# LB_i3_Button-v03_rev2.net
KiCad netlist of a schematic drawn in EAGLE
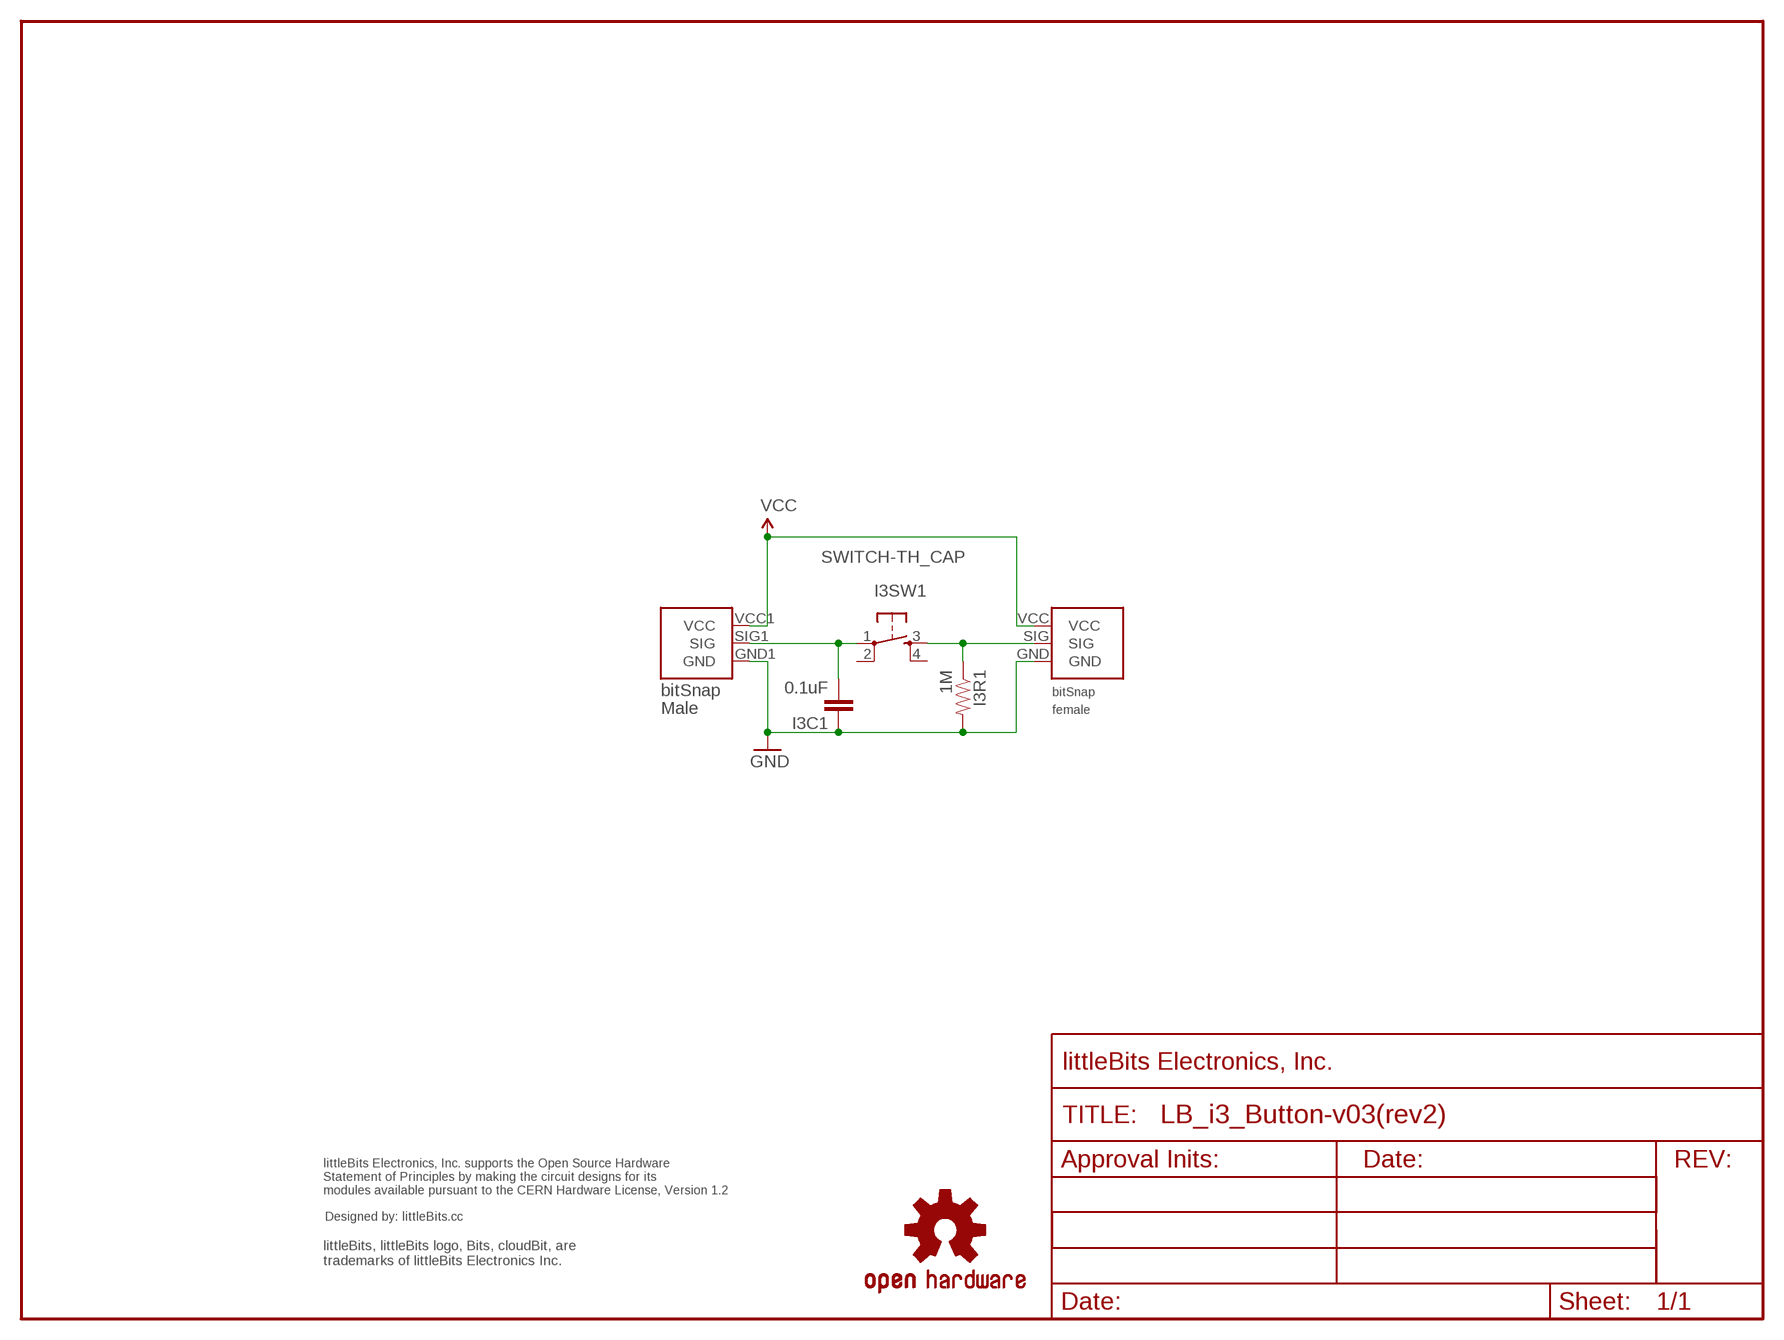
[diagram p0: schematic, sheet 1]

(export (version "E")
  (design (tool "Eeschema 10.0.6"))
  (components
    (comp (ref "I3BSF1")
      (value "BITSNAP_V03_FEMALE")
      (footprint "eagle-import:BITSNAP_V03_FEMALE")
      (libsource (lib "eagle-import") (part "BITSNAP_V03_FEMALE"))
    )
    (comp (ref "I3BSM1")
      (value "BITSNAP_V03_MALE")
      (footprint "eagle-import:BITSNAP_V03_MALE")
      (libsource (lib "eagle-import") (part "BITSNAP_V03_MALE"))
    )
    (comp (ref "I3C1")
      (value "0.1uF")
      (footprint "eagle-import:0603-CAP")
      (libsource (lib "eagle-import") (part "CAP0603-CAP"))
    )
    (comp (ref "I3R1")
      (value "1M")
      (footprint "eagle-import:0603-RES")
      (libsource (lib "eagle-import") (part "RESISTOR0603-RES"))
    )
    (comp (ref "I3SW1")
      (value "SWITCH-TH_CAP")
      (footprint "eagle-import:SWITCH-TH_CAP")
      (libsource (lib "eagle-import") (part "SWITCH-TH_CAP"))
    )
    (comp (ref "U$1")
      (value "OSHW-LOGOL")
      (footprint "eagle-import:OSHW-LOGO-L")
      (libsource (lib "eagle-import") (part "OSHW-LOGOL"))
    )
    (comp (ref "U$2")
      (value "FRAME-LETTER-OHWOHW")
      (footprint "eagle-import:FABDWG01-OHW")
      (libsource (lib "eagle-import") (part "FRAME-LETTER-OHWOHW"))
    )
    (comp (ref "U$5")
      (value "LB_CREDITS")
      (footprint "eagle-import:OSHWCREDIT")
      (libsource (lib "eagle-import") (part "LB_CREDITS"))
    )
  )
  (nets
    (net (code "1") (name "GND") (class "Default")
      (node (ref "I3BSF1") (pin "GND") (pinfunction "GND_GND") (pintype "bidirectional"))
      (node (ref "I3BSM1") (pin "GND1") (pinfunction "GND_GND1") (pintype "bidirectional"))
      (node (ref "I3C1") (pin "1") (pinfunction "1_1") (pintype "passive"))
      (node (ref "I3R1") (pin "2") (pinfunction "2_2") (pintype "passive"))
    )
    (net (code "2") (name "Net-(I3BSF1-PadSIG)") (class "Default")
      (node (ref "I3BSF1") (pin "SIG") (pinfunction "SIG_SIG") (pintype "bidirectional"))
      (node (ref "I3R1") (pin "1") (pinfunction "1_1") (pintype "passive"))
      (node (ref "I3SW1") (pin "3") (pinfunction "3_3") (pintype "passive"))
    )
    (net (code "3") (name "Net-(I3BSM1-SIG)") (class "Default")
      (node (ref "I3BSM1") (pin "SIG1") (pinfunction "SIG_SIG1") (pintype "bidirectional"))
      (node (ref "I3C1") (pin "2") (pinfunction "2_2") (pintype "passive"))
      (node (ref "I3SW1") (pin "1") (pinfunction "1_1") (pintype "passive"))
    )
    (net (code "4") (name "VCC") (class "Default")
      (node (ref "I3BSF1") (pin "VCC") (pinfunction "VCC_VCC") (pintype "bidirectional"))
      (node (ref "I3BSM1") (pin "VCC1") (pinfunction "VCC_VCC1") (pintype "bidirectional"))
    )
    (net (code "5") (name "unconnected-(I3SW1-Pad2)") (class "Default")
      (node (ref "I3SW1") (pin "2") (pinfunction "2_2") (pintype "passive"))
    )
    (net (code "6") (name "unconnected-(I3SW1-Pad4)") (class "Default")
      (node (ref "I3SW1") (pin "4") (pinfunction "4_4") (pintype "passive"))
    )
  )
)
